# POWER.net
KiCad netlist of a schematic drawn in Altium Designer
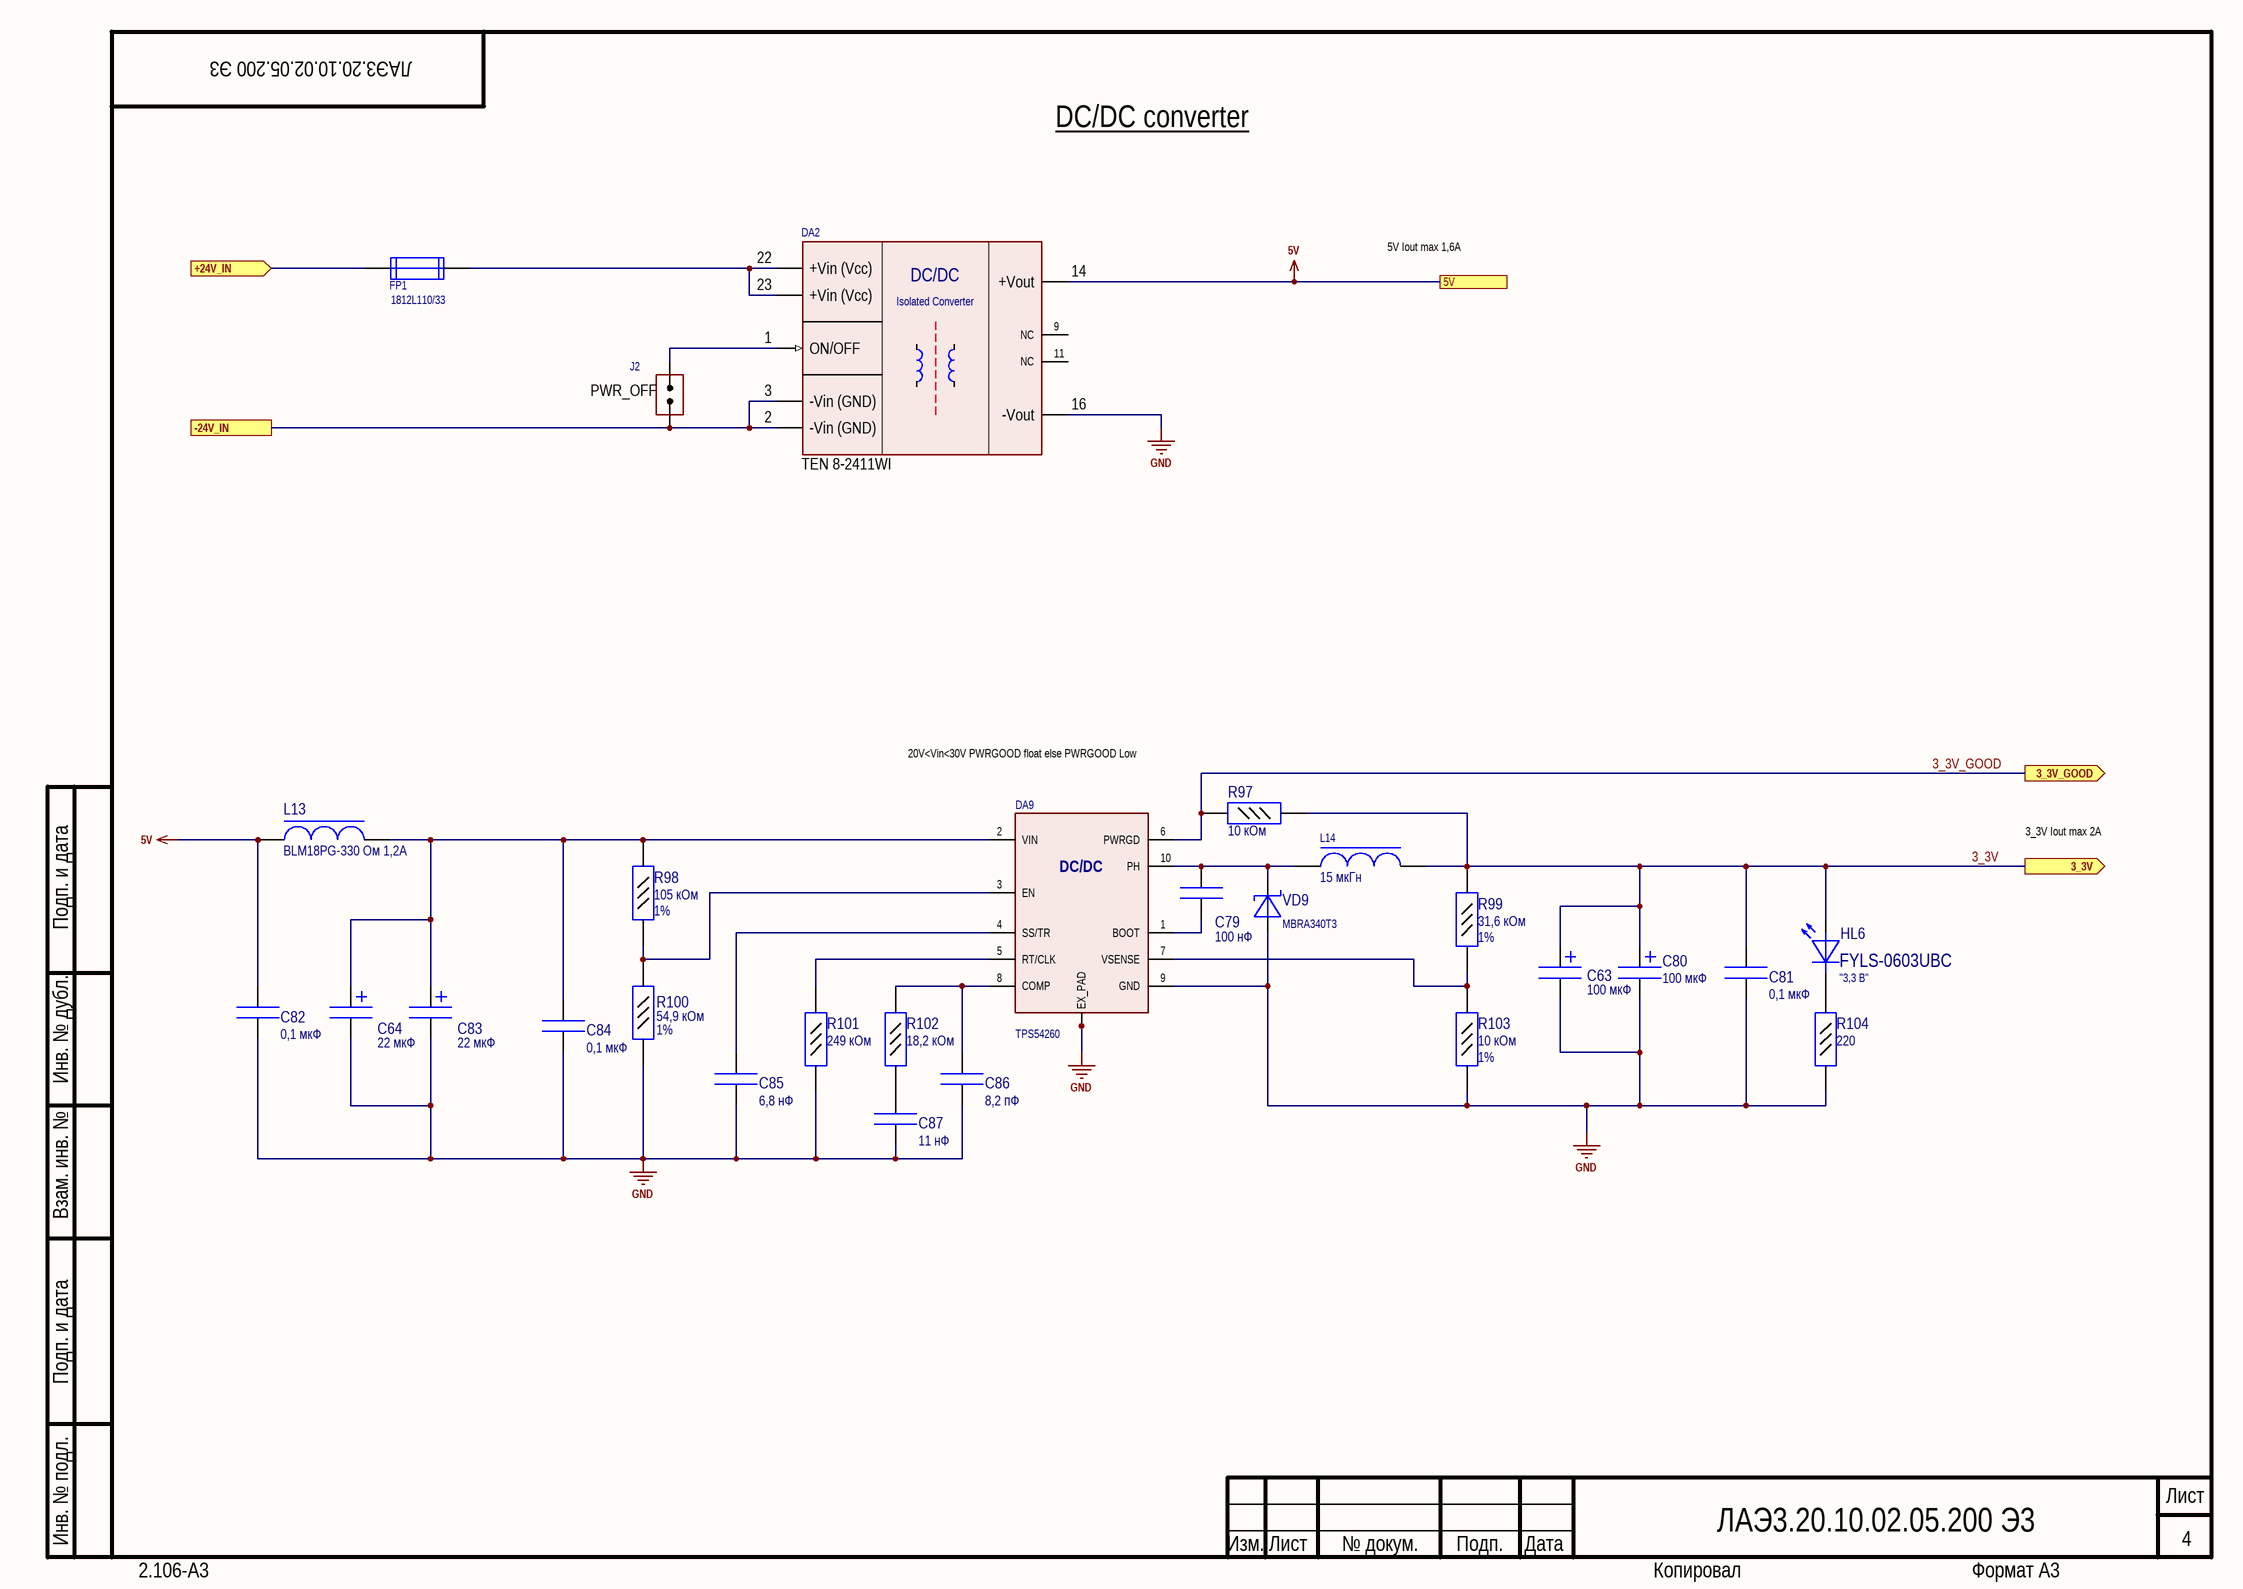
[diagram p0: POWER.SchDoc]

(export (version "E")
  (design (tool "Eeschema 10.0.6"))
  (components
    (comp (ref "C63")
      (value "100 мкФ")
      (footprint "CA-D (6.3x5.4)(0605)")
      (description "SMD ELECTROLYTIC CAPACITORS")
      (fields (field (name "Comment") "CA-16V100 мкФ-±20%-D (0605)"))
      (libsource (lib "Конденсаторы") (part "CA-16V-#-±20%-D (0605)"))
    )
    (comp (ref "C64")
      (value "22 мкФ")
      (footprint "CT-D")
      (description "Чип конденсатор  танталовый")
      (fields (field (name "Comment") "CT-35V-22uF-±20%-D"))
      (libsource (lib "Конденсаторы") (part "CT-35V-#-±20%-D"))
    )
    (comp (ref "C79")
      (value "100 нФ")
      (footprint "CC0603")
      (description "Чип конденсатор керамический")
      (fields (field (name "Comment") "CC0603-X7R-100 нФ-20%-50В"))
      (libsource (lib "Конденсаторы") (part "CC0603-X7R-#-20%-50В"))
    )
    (comp (ref "C80")
      (value "100 мкФ")
      (footprint "CA-D (6.3x5.4)(0605)")
      (description "SMD ELECTROLYTIC CAPACITORS")
      (fields (field (name "Comment") "CA-16V100 мкФ-±20%-D (0605)"))
      (libsource (lib "Конденсаторы") (part "CA-16V-#-±20%-D (0605)"))
    )
    (comp (ref "C81")
      (value "0,1 мкФ")
      (footprint "CC0603")
      (description "Чип конденсатор керамический")
      (fields (field (name "Comment") "CC0603-X7R-0,1 мкФ-20%-50В"))
      (libsource (lib "Конденсаторы") (part "CC0603-X7R-#-20%-50В"))
    )
    (comp (ref "C82")
      (value "0,1 мкФ")
      (footprint "CC0603")
      (description "Чип конденсатор керамический")
      (fields (field (name "Comment") "CC0603-X7R-0,1 мкФ-20%-50В"))
      (libsource (lib "Конденсаторы") (part "CC0603-X7R-#-20%-50В"))
    )
    (comp (ref "C83")
      (value "22 мкФ")
      (footprint "CT-D")
      (description "Чип конденсатор  танталовый")
      (fields (field (name "Comment") "CT-35V-22uF-±20%-D"))
      (libsource (lib "Конденсаторы") (part "CT-35V-#-±20%-D"))
    )
    (comp (ref "C84")
      (value "0,1 мкФ")
      (footprint "CC0603")
      (description "Чип конденсатор керамический")
      (fields (field (name "Comment") "CC0603-X7R-0,1 мкФ-20%-50В"))
      (libsource (lib "Конденсаторы") (part "CC0603-X7R-#-20%-50В"))
    )
    (comp (ref "C85")
      (value "6,8 нФ")
      (footprint "CC0603")
      (description "Чип конденсатор керамический")
      (fields (field (name "Comment") "CC0603-X7R-6,8 нФ-20%-50В"))
      (libsource (lib "Конденсаторы") (part "CC0603-X7R-#-20%-50В"))
    )
    (comp (ref "C86")
      (value "8,2 пФ")
      (footprint "CC0603")
      (description "Чип конденсатор керамический")
      (fields (field (name "Comment") "CC0603-X7R-8,2 пФ-20%-50В"))
      (libsource (lib "Конденсаторы") (part "CC0603-X7R-#-20%-50В"))
    )
    (comp (ref "C87")
      (value "11 нФ")
      (footprint "CC0603")
      (description "Чип конденсатор керамический")
      (fields (field (name "Comment") "CC0603-X7R-11 нФ-20%-50В"))
      (libsource (lib "Конденсаторы") (part "CC0603-X7R-#-20%-50В"))
    )
    (comp (ref "DA2")
      (value "TEN 8-2411WI")
      (footprint "TEN_8-2411WI")
      (description "9-36V input, 5V, 1.6 A output, 8 Watt dc/dc converter isolated 1500 VDC")
      (fields
        (field (name "MANUFACTURER") "TRACO POWER")
        (field (name "VALUEMANUFACTURERPARTNUMBER") "DC/DC converter, input 9...36V, 300 kHz, 5 V 1%, 1600 mA, -40...+85°C, metall DIP-24")
        (field (name "PARTNUMBER") "TEN 8-2411WI")
      )
      (libsource (lib "batmon_ICs") (part "TEN 8-2411WI"))
    )
    (comp (ref "DA9")
      (value "TPS54260")
      (footprint "IC_XTR111AIDGQR")
      (description "60-V,2.5-A,step-down regulator with an integrated high-side MOSFET")
      (fields (field (name "_VALUE") "TPS54260"))
      (libsource (lib "batmon_ICs") (part "TPS54260DGQ"))
    )
    (comp (ref "FP1")
      (value "1812L110/33")
      (footprint "MF-MSMD010")
      (description "сраб. 1,1 А, крит.1,95А")
      (libsource (lib "Предохранители") (part "MF-MSMD010"))
    )
    (comp (ref "HL6")
      (value "FYLS-0603UBC")
      (footprint "LED0603_Blue")
      (description "Светодиод синий SMD0603")
      (fields (field (name "MEAN") "\"3,3 В\""))
      (libsource (lib "Индикация") (part "FYLS-0603UBC"))
    )
    (comp (ref "J2")
      (value "~")
      (footprint "CON: PLS-2")
      (fields (field (name "COMMENTTEXT") "PWR_OFF"))
      (libsource (lib "Connector") (part "Jumper_single"))
    )
    (comp (ref "L13")
      (value "BLM18PG-330 Ом 1,2A")
      (footprint "CL0603")
      (description "Чип индуктивность подавления EMP")
      (libsource (lib "Индуктивности") (part "BLM18"))
    )
    (comp (ref "L14")
      (value "15 мкГн")
      (footprint "SRR0603")
      (description "Чип индуктивность 15 мкГн, 900 мА, Экранированный, 1.2 А")
      (fields (field (name "Comment") "SRR0603-150ML"))
      (libsource (lib "Индуктивности") (part "SRR0603"))
    )
    (comp (ref "R97")
      (value "10 кОм")
      (footprint "CR0603")
      (description "Чип резистор")
      (fields (field (name "Comment") "CR0603-10 кОм-±5%"))
      (libsource (lib "Резисторы") (part "CR0603-#-±5%"))
    )
    (comp (ref "R98")
      (value "105 кОм")
      (footprint "CR0603")
      (description "Чип резистор")
      (fields (field (name "TOLERANCE") "1%") (field (name "Comment") "CR0603-105 кОм-±1%"))
      (libsource (lib "Резисторы") (part "CR0603-#-±1%"))
    )
    (comp (ref "R99")
      (value "31,6 кОм")
      (footprint "CR0603")
      (description "Чип резистор")
      (fields (field (name "TOLERANCE") "1%") (field (name "Comment") "CR0603-31,6 кОм-±1%"))
      (libsource (lib "Резисторы") (part "CR0603-#-±1%"))
    )
    (comp (ref "R100")
      (value "54,9 кОм")
      (footprint "CR0603")
      (description "Чип резистор")
      (fields (field (name "TOLERANCE") "1%") (field (name "Comment") "CR0603-54,9 кОм-±1%"))
      (libsource (lib "Резисторы") (part "CR0603-#-±1%"))
    )
    (comp (ref "R101")
      (value "249 кОм")
      (footprint "CR0603")
      (description "Чип резистор")
      (fields (field (name "Comment") "CR0603-249 кОм-±5%"))
      (libsource (lib "") (part "CR0603-#-±5%_1"))
    )
    (comp (ref "R102")
      (value "18,2 кОм")
      (footprint "CR0603")
      (description "Чип резистор")
      (fields (field (name "Comment") "CR0603-18,2 кОм-±5%"))
      (libsource (lib "") (part "CR0603-#-±5%_1"))
    )
    (comp (ref "R103")
      (value "10 кОм")
      (footprint "CR0603")
      (description "Чип резистор")
      (fields (field (name "TOLERANCE") "1%") (field (name "Comment") "CR0603-10 кОм-±1%"))
      (libsource (lib "Резисторы") (part "CR0603-#-±1%"))
    )
    (comp (ref "R104")
      (value "220")
      (footprint "CR0603")
      (description "Чип резистор")
      (fields (field (name "Comment") "CR0603-220-±5%"))
      (libsource (lib "") (part "CR0603-#-±5%_2"))
    )
    (comp (ref "VD9")
      (value "MBRA340T3")
      (footprint "DO-214AC (SMA)")
      (description "Диод шотки I=3А V=40В")
      (libsource (lib "Диоды") (part "MBRA340T3"))
    )
  )
  (nets
    (net (code "1") (name "/+24V_IN") (class "Default")
      (node (ref "FP1") (pin "1") (pinfunction "+_1") (pintype "passive"))
    )
    (net (code "2") (name "/-24V_IN") (class "Default")
      (node (ref "DA2") (pin "2") (pinfunction "-Vin_(GND)_2") (pintype "power_in"))
      (node (ref "DA2") (pin "3") (pinfunction "-Vin_(GND)_3") (pintype "power_in"))
      (node (ref "J2") (pin "2") (pinfunction "IN_2") (pintype "passive"))
    )
    (net (code "3") (name "/3_3V") (class "Default")
      (node (ref "C63") (pin "1") (pinfunction "+_1") (pintype "passive"))
      (node (ref "C80") (pin "1") (pinfunction "+_1") (pintype "passive"))
      (node (ref "C81") (pin "1") (pinfunction "+_1") (pintype "passive"))
      (node (ref "HL6") (pin "1") (pinfunction "A_1") (pintype "passive"))
      (node (ref "L14") (pin "2") (pinfunction "2_2") (pintype "passive"))
      (node (ref "R97") (pin "1") (pinfunction "+_1") (pintype "passive"))
      (node (ref "R99") (pin "2") (pinfunction "-_2") (pintype "passive"))
    )
    (net (code "4") (name "/3_3V_GOOD") (class "Default")
      (node (ref "DA9") (pin "6") (pinfunction "PWRGD_6") (pintype "passive"))
      (node (ref "R97") (pin "2") (pinfunction "-_2") (pintype "passive"))
    )
    (net (code "5") (name "5V") (class "Default")
      (node (ref "C82") (pin "1") (pinfunction "+_1") (pintype "passive"))
      (node (ref "DA2") (pin "14") (pinfunction "+Vout_14") (pintype "power_in"))
      (node (ref "L13") (pin "1") (pinfunction "1_1") (pintype "passive"))
    )
    (net (code "6") (name "GND") (class "Default")
      (node (ref "C63") (pin "2") (pinfunction "-_2") (pintype "passive"))
      (node (ref "C64") (pin "2") (pinfunction "-_2") (pintype "passive"))
      (node (ref "C80") (pin "2") (pinfunction "-_2") (pintype "passive"))
      (node (ref "C81") (pin "2") (pinfunction "-_2") (pintype "passive"))
      (node (ref "C82") (pin "2") (pinfunction "-_2") (pintype "passive"))
      (node (ref "C83") (pin "2") (pinfunction "-_2") (pintype "passive"))
      (node (ref "C84") (pin "2") (pinfunction "-_2") (pintype "passive"))
      (node (ref "C85") (pin "2") (pinfunction "-_2") (pintype "passive"))
      (node (ref "C86") (pin "2") (pinfunction "-_2") (pintype "passive"))
      (node (ref "C87") (pin "2") (pinfunction "-_2") (pintype "passive"))
      (node (ref "DA2") (pin "16") (pinfunction "-Vout_16") (pintype "power_in"))
      (node (ref "DA9") (pin "11") (pinfunction "EX_PAD_11") (pintype "power_in"))
      (node (ref "DA9") (pin "12") (pinfunction "EX_PAD_12") (pintype "power_in"))
      (node (ref "DA9") (pin "13") (pinfunction "EX_PAD_13") (pintype "power_in"))
      (node (ref "DA9") (pin "14") (pinfunction "EX_PAD_14") (pintype "power_in"))
      (node (ref "DA9") (pin "15") (pinfunction "EX_PAD_15") (pintype "power_in"))
      (node (ref "DA9") (pin "16") (pinfunction "EX_PAD_16") (pintype "power_in"))
      (node (ref "DA9") (pin "9") (pinfunction "GND_9") (pintype "power_in"))
      (node (ref "R100") (pin "1") (pinfunction "+_1") (pintype "passive"))
      (node (ref "R101") (pin "1") (pinfunction "+_1") (pintype "passive"))
      (node (ref "R103") (pin "1") (pinfunction "+_1") (pintype "passive"))
      (node (ref "R104") (pin "2") (pinfunction "-_2") (pintype "passive"))
      (node (ref "VD9") (pin "1") (pinfunction "+_1") (pintype "passive"))
    )
    (net (code "7") (name "Net-(C64-+)") (class "Default")
      (node (ref "C64") (pin "1") (pinfunction "+_1") (pintype "passive"))
      (node (ref "C83") (pin "1") (pinfunction "+_1") (pintype "passive"))
      (node (ref "C84") (pin "1") (pinfunction "+_1") (pintype "passive"))
      (node (ref "DA9") (pin "2") (pinfunction "VIN_2") (pintype "power_in"))
      (node (ref "L13") (pin "2") (pinfunction "2_2") (pintype "passive"))
      (node (ref "R98") (pin "2") (pinfunction "-_2") (pintype "passive"))
    )
    (net (code "8") (name "Net-(C79-+)") (class "Default")
      (node (ref "C79") (pin "1") (pinfunction "+_1") (pintype "passive"))
      (node (ref "DA9") (pin "10") (pinfunction "PH_10") (pintype "passive"))
      (node (ref "L14") (pin "1") (pinfunction "1_1") (pintype "passive"))
      (node (ref "VD9") (pin "2") (pinfunction "-_2") (pintype "passive"))
    )
    (net (code "9") (name "Net-(C79--)") (class "Default")
      (node (ref "C79") (pin "2") (pinfunction "-_2") (pintype "passive"))
      (node (ref "DA9") (pin "1") (pinfunction "BOOT_1") (pintype "passive"))
    )
    (net (code "10") (name "Net-(C85-+)") (class "Default")
      (node (ref "C85") (pin "1") (pinfunction "+_1") (pintype "passive"))
      (node (ref "DA9") (pin "4") (pinfunction "SS/TR_4") (pintype "passive"))
    )
    (net (code "11") (name "Net-(C86-+)") (class "Default")
      (node (ref "C86") (pin "1") (pinfunction "+_1") (pintype "passive"))
      (node (ref "DA9") (pin "8") (pinfunction "COMP_8") (pintype "passive"))
      (node (ref "R102") (pin "2") (pinfunction "-_2") (pintype "passive"))
    )
    (net (code "12") (name "Net-(C87-+)") (class "Default")
      (node (ref "C87") (pin "1") (pinfunction "+_1") (pintype "passive"))
      (node (ref "R102") (pin "1") (pinfunction "+_1") (pintype "passive"))
    )
    (net (code "13") (name "Net-(DA2-ON{slash}OFF)") (class "Default")
      (node (ref "DA2") (pin "1") (pinfunction "ON/OFF_1") (pintype "input"))
      (node (ref "J2") (pin "1") (pinfunction "IN_1") (pintype "passive"))
    )
    (net (code "14") (name "Net-(DA9-EN)") (class "Default")
      (node (ref "DA9") (pin "3") (pinfunction "EN_3") (pintype "passive"))
      (node (ref "R100") (pin "2") (pinfunction "-_2") (pintype "passive"))
      (node (ref "R98") (pin "1") (pinfunction "+_1") (pintype "passive"))
    )
    (net (code "15") (name "Net-(DA9-RT{slash}CLK)") (class "Default")
      (node (ref "DA9") (pin "5") (pinfunction "RT/CLK_5") (pintype "passive"))
      (node (ref "R101") (pin "2") (pinfunction "-_2") (pintype "passive"))
    )
    (net (code "16") (name "Net-(DA9-VSENSE)") (class "Default")
      (node (ref "DA9") (pin "7") (pinfunction "VSENSE_7") (pintype "passive"))
      (node (ref "R103") (pin "2") (pinfunction "-_2") (pintype "passive"))
      (node (ref "R99") (pin "1") (pinfunction "+_1") (pintype "passive"))
    )
    (net (code "17") (name "Net-(FP1--)") (class "Default")
      (node (ref "DA2") (pin "22") (pinfunction "+Vin_(Vcc)_22") (pintype "power_in"))
      (node (ref "DA2") (pin "23") (pinfunction "+Vin_(Vcc)_23") (pintype "power_in"))
      (node (ref "FP1") (pin "2") (pinfunction "-_2") (pintype "passive"))
    )
    (net (code "18") (name "Net-(HL6-K)") (class "Default")
      (node (ref "HL6") (pin "2") (pinfunction "K_2") (pintype "passive"))
      (node (ref "R104") (pin "1") (pinfunction "+_1") (pintype "passive"))
    )
    (net (code "19") (name "unconnected-(DA2-NC-Pad9)") (class "Default")
      (node (ref "DA2") (pin "9") (pinfunction "NC_9") (pintype "passive"))
    )
    (net (code "20") (name "unconnected-(DA2-NC-Pad11)") (class "Default")
      (node (ref "DA2") (pin "11") (pinfunction "NC_11") (pintype "passive"))
    )
  )
)
